# Resistor.net
KiCad netlist of a schematic drawn in Altium Designer
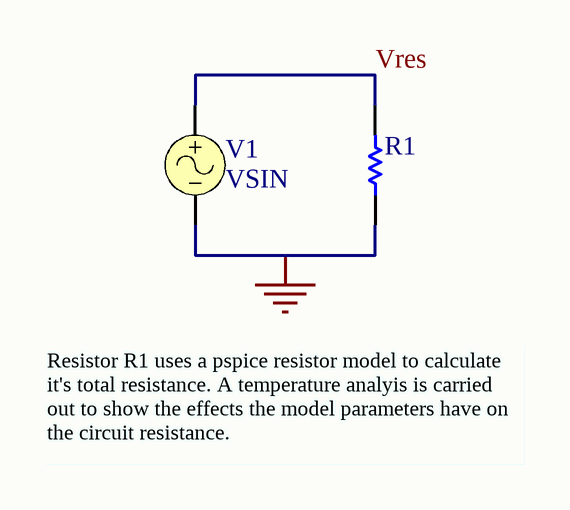
[diagram p0: Resistor.SchDoc]

(export (version "E")
  (design (tool "Eeschema 10.0.6"))
  (components
    (comp (ref "R1")
      (value "Res1")
      (footprint "AXIAL-0.3")
      (description "Resistor")
      (fields (field (name "PUBLISHER") "Altium Limited"))
      (libsource (lib "Miscellaneous Devices") (part "Res1"))
    )
    (comp (ref "V1")
      (value "VSIN")
      (description "Sinusoidal Voltage Source")
      (fields (field (name "PUBLISHER") "Altium Limited"))
      (libsource (lib "Simulation Sources") (part "VSIN"))
    )
  )
  (nets
    (net (code "1") (name "/Vres") (class "Default")
      (node (ref "R1") (pin "2") (pinfunction "2_2") (pintype "passive"))
      (node (ref "V1") (pin "1") (pinfunction "1_1") (pintype "passive"))
    )
    (net (code "3") (name "GND") (class "Default")
      (node (ref "R1") (pin "1") (pinfunction "1_1") (pintype "passive"))
      (node (ref "V1") (pin "2") (pinfunction "2_2") (pintype "passive"))
    )
  )
)
